# 03_ZYNQ_Power.net
KiCad netlist of a schematic drawn in Altium Designer
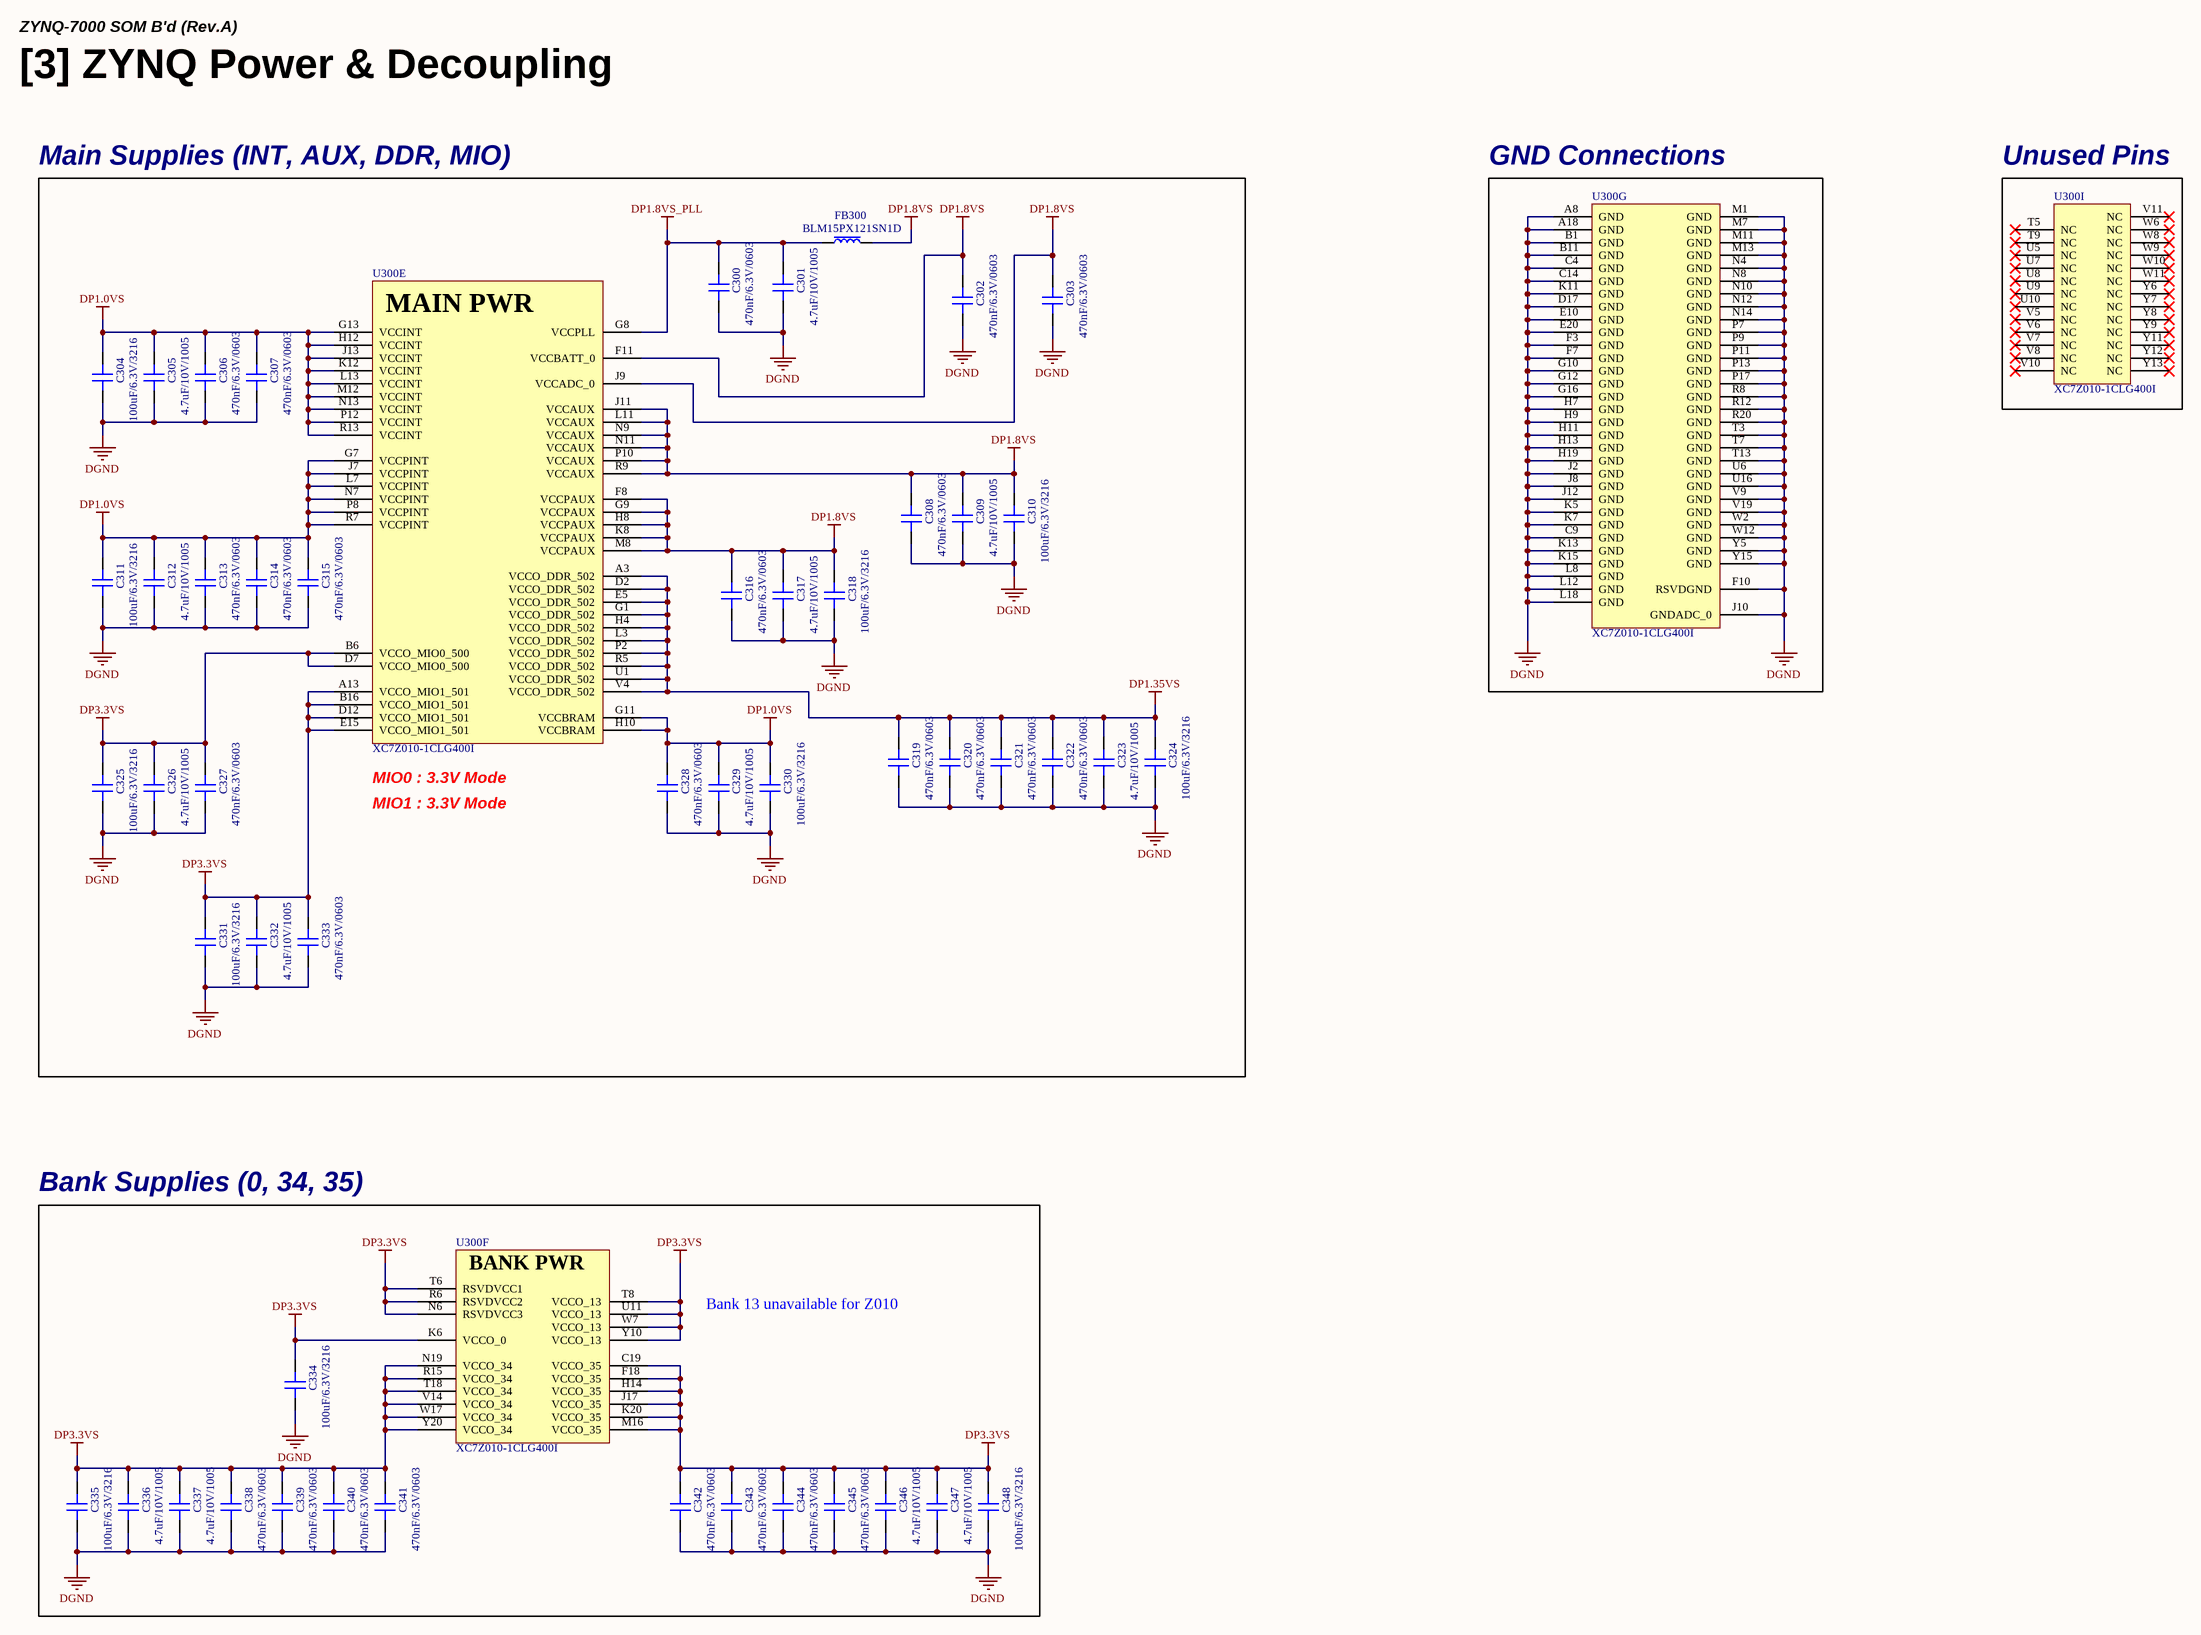
[diagram p0: 03_ZYNQ_Power.SchDoc]

(export (version "E")
  (design (tool "Eeschema 10.0.6"))
  (components
    (comp (ref "C300")
      (value "470nF/6.3V/0603")
      (footprint "CAP 0603 (0201_INCH)")
      (description "6.3V 470nF X5R ±10% 0201  Multilayer Ceramic Capacitors MLCC - SMD/SMT ROHS")
      (fields (field (name "LCSC PART #") "C85926"))
      (libsource (lib "Arkx") (part "CAP_470nF/6.3V/0603"))
    )
    (comp (ref "C301")
      (value "4.7uF/10V/1005")
      (footprint "CAP 1005 (0402_INCH)")
      (description "10V 4.7uF X5R ±20% 0402  Multilayer Ceramic Capacitors MLCC - SMD/SMT ROHS")
      (fields (field (name "LCSC PART #") "C23733"))
      (libsource (lib "Arkx") (part "CAP_4.7uF/10V/1005"))
    )
    (comp (ref "C302")
      (value "470nF/6.3V/0603")
      (footprint "CAP 0603 (0201_INCH)")
      (description "6.3V 470nF X5R ±10% 0201  Multilayer Ceramic Capacitors MLCC - SMD/SMT ROHS")
      (fields (field (name "LCSC PART #") "C85926"))
      (libsource (lib "Arkx") (part "CAP_470nF/6.3V/0603"))
    )
    (comp (ref "C303")
      (value "470nF/6.3V/0603")
      (footprint "CAP 0603 (0201_INCH)")
      (description "6.3V 470nF X5R ±10% 0201  Multilayer Ceramic Capacitors MLCC - SMD/SMT ROHS")
      (fields (field (name "LCSC PART #") "C85926"))
      (libsource (lib "Arkx") (part "CAP_470nF/6.3V/0603"))
    )
    (comp (ref "C304")
      (value "100uF/6.3V/3216")
      (footprint "CAP 3216 (1206_INCH) - H1.8MM")
      (description "Ceramic CAP_100uF/6.3V/3216")
      (fields (field (name "LCSC PART #") "C15008"))
      (libsource (lib "Arkx") (part "CAP_100uF/6.3V/3216"))
    )
    (comp (ref "C305")
      (value "4.7uF/10V/1005")
      (footprint "CAP 1005 (0402_INCH)")
      (description "10V 4.7uF X5R ±20% 0402  Multilayer Ceramic Capacitors MLCC - SMD/SMT ROHS")
      (fields (field (name "LCSC PART #") "C23733"))
      (libsource (lib "Arkx") (part "CAP_4.7uF/10V/1005"))
    )
    (comp (ref "C306")
      (value "470nF/6.3V/0603")
      (footprint "CAP 0603 (0201_INCH)")
      (description "6.3V 470nF X5R ±10% 0201  Multilayer Ceramic Capacitors MLCC - SMD/SMT ROHS")
      (fields (field (name "LCSC PART #") "C85926"))
      (libsource (lib "Arkx") (part "CAP_470nF/6.3V/0603"))
    )
    (comp (ref "C307")
      (value "470nF/6.3V/0603")
      (footprint "CAP 0603 (0201_INCH)")
      (description "6.3V 470nF X5R ±10% 0201  Multilayer Ceramic Capacitors MLCC - SMD/SMT ROHS")
      (fields (field (name "LCSC PART #") "C85926"))
      (libsource (lib "Arkx") (part "CAP_470nF/6.3V/0603"))
    )
    (comp (ref "C308")
      (value "470nF/6.3V/0603")
      (footprint "CAP 0603 (0201_INCH)")
      (description "6.3V 470nF X5R ±10% 0201  Multilayer Ceramic Capacitors MLCC - SMD/SMT ROHS")
      (fields (field (name "LCSC PART #") "C85926"))
      (libsource (lib "Arkx") (part "CAP_470nF/6.3V/0603"))
    )
    (comp (ref "C309")
      (value "4.7uF/10V/1005")
      (footprint "CAP 1005 (0402_INCH)")
      (description "10V 4.7uF X5R ±20% 0402  Multilayer Ceramic Capacitors MLCC - SMD/SMT ROHS")
      (fields (field (name "LCSC PART #") "C23733"))
      (libsource (lib "Arkx") (part "CAP_4.7uF/10V/1005"))
    )
    (comp (ref "C310")
      (value "100uF/6.3V/3216")
      (footprint "CAP 3216 (1206_INCH) - H1.8MM")
      (description "Ceramic CAP_100uF/6.3V/3216")
      (fields (field (name "LCSC PART #") "C15008"))
      (libsource (lib "Arkx") (part "CAP_100uF/6.3V/3216"))
    )
    (comp (ref "C311")
      (value "100uF/6.3V/3216")
      (footprint "CAP 3216 (1206_INCH) - H1.8MM")
      (description "Ceramic CAP_100uF/6.3V/3216")
      (fields (field (name "LCSC PART #") "C15008"))
      (libsource (lib "Arkx") (part "CAP_100uF/6.3V/3216"))
    )
    (comp (ref "C312")
      (value "4.7uF/10V/1005")
      (footprint "CAP 1005 (0402_INCH)")
      (description "10V 4.7uF X5R ±20% 0402  Multilayer Ceramic Capacitors MLCC - SMD/SMT ROHS")
      (fields (field (name "LCSC PART #") "C23733"))
      (libsource (lib "Arkx") (part "CAP_4.7uF/10V/1005"))
    )
    (comp (ref "C313")
      (value "470nF/6.3V/0603")
      (footprint "CAP 0603 (0201_INCH)")
      (description "6.3V 470nF X5R ±10% 0201  Multilayer Ceramic Capacitors MLCC - SMD/SMT ROHS")
      (fields (field (name "LCSC PART #") "C85926"))
      (libsource (lib "Arkx") (part "CAP_470nF/6.3V/0603"))
    )
    (comp (ref "C314")
      (value "470nF/6.3V/0603")
      (footprint "CAP 0603 (0201_INCH)")
      (description "6.3V 470nF X5R ±10% 0201  Multilayer Ceramic Capacitors MLCC - SMD/SMT ROHS")
      (fields (field (name "LCSC PART #") "C85926"))
      (libsource (lib "Arkx") (part "CAP_470nF/6.3V/0603"))
    )
    (comp (ref "C315")
      (value "470nF/6.3V/0603")
      (footprint "CAP 0603 (0201_INCH)")
      (description "6.3V 470nF X5R ±10% 0201  Multilayer Ceramic Capacitors MLCC - SMD/SMT ROHS")
      (fields (field (name "LCSC PART #") "C85926"))
      (libsource (lib "Arkx") (part "CAP_470nF/6.3V/0603"))
    )
    (comp (ref "C316")
      (value "470nF/6.3V/0603")
      (footprint "CAP 0603 (0201_INCH)")
      (description "6.3V 470nF X5R ±10% 0201  Multilayer Ceramic Capacitors MLCC - SMD/SMT ROHS")
      (fields (field (name "LCSC PART #") "C85926"))
      (libsource (lib "Arkx") (part "CAP_470nF/6.3V/0603"))
    )
    (comp (ref "C317")
      (value "4.7uF/10V/1005")
      (footprint "CAP 1005 (0402_INCH)")
      (description "10V 4.7uF X5R ±20% 0402  Multilayer Ceramic Capacitors MLCC - SMD/SMT ROHS")
      (fields (field (name "LCSC PART #") "C23733"))
      (libsource (lib "Arkx") (part "CAP_4.7uF/10V/1005"))
    )
    (comp (ref "C318")
      (value "100uF/6.3V/3216")
      (footprint "CAP 3216 (1206_INCH) - H1.8MM")
      (description "Ceramic CAP_100uF/6.3V/3216")
      (fields (field (name "LCSC PART #") "C15008"))
      (libsource (lib "Arkx") (part "CAP_100uF/6.3V/3216"))
    )
    (comp (ref "C319")
      (value "470nF/6.3V/0603")
      (footprint "CAP 0603 (0201_INCH)")
      (description "6.3V 470nF X5R ±10% 0201  Multilayer Ceramic Capacitors MLCC - SMD/SMT ROHS")
      (fields (field (name "LCSC PART #") "C85926"))
      (libsource (lib "Arkx") (part "CAP_470nF/6.3V/0603"))
    )
    (comp (ref "C320")
      (value "470nF/6.3V/0603")
      (footprint "CAP 0603 (0201_INCH)")
      (description "6.3V 470nF X5R ±10% 0201  Multilayer Ceramic Capacitors MLCC - SMD/SMT ROHS")
      (fields (field (name "LCSC PART #") "C85926"))
      (libsource (lib "Arkx") (part "CAP_470nF/6.3V/0603"))
    )
    (comp (ref "C321")
      (value "470nF/6.3V/0603")
      (footprint "CAP 0603 (0201_INCH)")
      (description "6.3V 470nF X5R ±10% 0201  Multilayer Ceramic Capacitors MLCC - SMD/SMT ROHS")
      (fields (field (name "LCSC PART #") "C85926"))
      (libsource (lib "Arkx") (part "CAP_470nF/6.3V/0603"))
    )
    (comp (ref "C322")
      (value "470nF/6.3V/0603")
      (footprint "CAP 0603 (0201_INCH)")
      (description "6.3V 470nF X5R ±10% 0201  Multilayer Ceramic Capacitors MLCC - SMD/SMT ROHS")
      (fields (field (name "LCSC PART #") "C85926"))
      (libsource (lib "Arkx") (part "CAP_470nF/6.3V/0603"))
    )
    (comp (ref "C323")
      (value "4.7uF/10V/1005")
      (footprint "CAP 1005 (0402_INCH)")
      (description "10V 4.7uF X5R ±20% 0402  Multilayer Ceramic Capacitors MLCC - SMD/SMT ROHS")
      (fields (field (name "LCSC PART #") "C23733"))
      (libsource (lib "Arkx") (part "CAP_4.7uF/10V/1005"))
    )
    (comp (ref "C324")
      (value "100uF/6.3V/3216")
      (footprint "CAP 3216 (1206_INCH) - H1.8MM")
      (description "Ceramic CAP_100uF/6.3V/3216")
      (fields (field (name "LCSC PART #") "C15008"))
      (libsource (lib "Arkx") (part "CAP_100uF/6.3V/3216"))
    )
    (comp (ref "C325")
      (value "100uF/6.3V/3216")
      (footprint "CAP 3216 (1206_INCH) - H1.8MM")
      (description "Ceramic CAP_100uF/6.3V/3216")
      (fields (field (name "LCSC PART #") "C15008"))
      (libsource (lib "Arkx") (part "CAP_100uF/6.3V/3216"))
    )
    (comp (ref "C326")
      (value "4.7uF/10V/1005")
      (footprint "CAP 1005 (0402_INCH)")
      (description "10V 4.7uF X5R ±20% 0402  Multilayer Ceramic Capacitors MLCC - SMD/SMT ROHS")
      (fields (field (name "LCSC PART #") "C23733"))
      (libsource (lib "Arkx") (part "CAP_4.7uF/10V/1005"))
    )
    (comp (ref "C327")
      (value "470nF/6.3V/0603")
      (footprint "CAP 0603 (0201_INCH)")
      (description "6.3V 470nF X5R ±10% 0201  Multilayer Ceramic Capacitors MLCC - SMD/SMT ROHS")
      (fields (field (name "LCSC PART #") "C85926"))
      (libsource (lib "Arkx") (part "CAP_470nF/6.3V/0603"))
    )
    (comp (ref "C328")
      (value "470nF/6.3V/0603")
      (footprint "CAP 0603 (0201_INCH)")
      (description "6.3V 470nF X5R ±10% 0201  Multilayer Ceramic Capacitors MLCC - SMD/SMT ROHS")
      (fields (field (name "LCSC PART #") "C85926"))
      (libsource (lib "Arkx") (part "CAP_470nF/6.3V/0603"))
    )
    (comp (ref "C329")
      (value "4.7uF/10V/1005")
      (footprint "CAP 1005 (0402_INCH)")
      (description "10V 4.7uF X5R ±20% 0402  Multilayer Ceramic Capacitors MLCC - SMD/SMT ROHS")
      (fields (field (name "LCSC PART #") "C23733"))
      (libsource (lib "Arkx") (part "CAP_4.7uF/10V/1005"))
    )
    (comp (ref "C330")
      (value "100uF/6.3V/3216")
      (footprint "CAP 3216 (1206_INCH) - H1.8MM")
      (description "Ceramic CAP_100uF/6.3V/3216")
      (fields (field (name "LCSC PART #") "C15008"))
      (libsource (lib "Arkx") (part "CAP_100uF/6.3V/3216"))
    )
    (comp (ref "C331")
      (value "100uF/6.3V/3216")
      (footprint "CAP 3216 (1206_INCH) - H1.8MM")
      (description "Ceramic CAP_100uF/6.3V/3216")
      (fields (field (name "LCSC PART #") "C15008"))
      (libsource (lib "Arkx") (part "CAP_100uF/6.3V/3216"))
    )
    (comp (ref "C332")
      (value "4.7uF/10V/1005")
      (footprint "CAP 1005 (0402_INCH)")
      (description "10V 4.7uF X5R ±20% 0402  Multilayer Ceramic Capacitors MLCC - SMD/SMT ROHS")
      (fields (field (name "LCSC PART #") "C23733"))
      (libsource (lib "Arkx") (part "CAP_4.7uF/10V/1005"))
    )
    (comp (ref "C333")
      (value "470nF/6.3V/0603")
      (footprint "CAP 0603 (0201_INCH)")
      (description "6.3V 470nF X5R ±10% 0201  Multilayer Ceramic Capacitors MLCC - SMD/SMT ROHS")
      (fields (field (name "LCSC PART #") "C85926"))
      (libsource (lib "Arkx") (part "CAP_470nF/6.3V/0603"))
    )
    (comp (ref "C334")
      (value "100uF/6.3V/3216")
      (footprint "CAP 3216 (1206_INCH) - H1.8MM")
      (description "Ceramic CAP_100uF/6.3V/3216")
      (fields (field (name "LCSC PART #") "C15008"))
      (libsource (lib "Arkx") (part "CAP_100uF/6.3V/3216"))
    )
    (comp (ref "C335")
      (value "100uF/6.3V/3216")
      (footprint "CAP 3216 (1206_INCH) - H1.8MM")
      (description "Ceramic CAP_100uF/6.3V/3216")
      (fields (field (name "LCSC PART #") "C15008"))
      (libsource (lib "Arkx") (part "CAP_100uF/6.3V/3216"))
    )
    (comp (ref "C336")
      (value "4.7uF/10V/1005")
      (footprint "CAP 1005 (0402_INCH)")
      (description "10V 4.7uF X5R ±20% 0402  Multilayer Ceramic Capacitors MLCC - SMD/SMT ROHS")
      (fields (field (name "LCSC PART #") "C23733"))
      (libsource (lib "Arkx") (part "CAP_4.7uF/10V/1005"))
    )
    (comp (ref "C337")
      (value "4.7uF/10V/1005")
      (footprint "CAP 1005 (0402_INCH)")
      (description "10V 4.7uF X5R ±20% 0402  Multilayer Ceramic Capacitors MLCC - SMD/SMT ROHS")
      (fields (field (name "LCSC PART #") "C23733"))
      (libsource (lib "Arkx") (part "CAP_4.7uF/10V/1005"))
    )
    (comp (ref "C338")
      (value "470nF/6.3V/0603")
      (footprint "CAP 0603 (0201_INCH)")
      (description "6.3V 470nF X5R ±10% 0201  Multilayer Ceramic Capacitors MLCC - SMD/SMT ROHS")
      (fields (field (name "LCSC PART #") "C85926"))
      (libsource (lib "Arkx") (part "CAP_470nF/6.3V/0603"))
    )
    (comp (ref "C339")
      (value "470nF/6.3V/0603")
      (footprint "CAP 0603 (0201_INCH)")
      (description "6.3V 470nF X5R ±10% 0201  Multilayer Ceramic Capacitors MLCC - SMD/SMT ROHS")
      (fields (field (name "LCSC PART #") "C85926"))
      (libsource (lib "Arkx") (part "CAP_470nF/6.3V/0603"))
    )
    (comp (ref "C340")
      (value "470nF/6.3V/0603")
      (footprint "CAP 0603 (0201_INCH)")
      (description "6.3V 470nF X5R ±10% 0201  Multilayer Ceramic Capacitors MLCC - SMD/SMT ROHS")
      (fields (field (name "LCSC PART #") "C85926"))
      (libsource (lib "Arkx") (part "CAP_470nF/6.3V/0603"))
    )
    (comp (ref "C341")
      (value "470nF/6.3V/0603")
      (footprint "CAP 0603 (0201_INCH)")
      (description "6.3V 470nF X5R ±10% 0201  Multilayer Ceramic Capacitors MLCC - SMD/SMT ROHS")
      (fields (field (name "LCSC PART #") "C85926"))
      (libsource (lib "Arkx") (part "CAP_470nF/6.3V/0603"))
    )
    (comp (ref "C342")
      (value "470nF/6.3V/0603")
      (footprint "CAP 0603 (0201_INCH)")
      (description "6.3V 470nF X5R ±10% 0201  Multilayer Ceramic Capacitors MLCC - SMD/SMT ROHS")
      (fields (field (name "LCSC PART #") "C85926"))
      (libsource (lib "Arkx") (part "CAP_470nF/6.3V/0603"))
    )
    (comp (ref "C343")
      (value "470nF/6.3V/0603")
      (footprint "CAP 0603 (0201_INCH)")
      (description "6.3V 470nF X5R ±10% 0201  Multilayer Ceramic Capacitors MLCC - SMD/SMT ROHS")
      (fields (field (name "LCSC PART #") "C85926"))
      (libsource (lib "Arkx") (part "CAP_470nF/6.3V/0603"))
    )
    (comp (ref "C344")
      (value "470nF/6.3V/0603")
      (footprint "CAP 0603 (0201_INCH)")
      (description "6.3V 470nF X5R ±10% 0201  Multilayer Ceramic Capacitors MLCC - SMD/SMT ROHS")
      (fields (field (name "LCSC PART #") "C85926"))
      (libsource (lib "Arkx") (part "CAP_470nF/6.3V/0603"))
    )
    (comp (ref "C345")
      (value "470nF/6.3V/0603")
      (footprint "CAP 0603 (0201_INCH)")
      (description "6.3V 470nF X5R ±10% 0201  Multilayer Ceramic Capacitors MLCC - SMD/SMT ROHS")
      (fields (field (name "LCSC PART #") "C85926"))
      (libsource (lib "Arkx") (part "CAP_470nF/6.3V/0603"))
    )
    (comp (ref "C346")
      (value "4.7uF/10V/1005")
      (footprint "CAP 1005 (0402_INCH)")
      (description "10V 4.7uF X5R ±20% 0402  Multilayer Ceramic Capacitors MLCC - SMD/SMT ROHS")
      (fields (field (name "LCSC PART #") "C23733"))
      (libsource (lib "Arkx") (part "CAP_4.7uF/10V/1005"))
    )
    (comp (ref "C347")
      (value "4.7uF/10V/1005")
      (footprint "CAP 1005 (0402_INCH)")
      (description "10V 4.7uF X5R ±20% 0402  Multilayer Ceramic Capacitors MLCC - SMD/SMT ROHS")
      (fields (field (name "LCSC PART #") "C23733"))
      (libsource (lib "Arkx") (part "CAP_4.7uF/10V/1005"))
    )
    (comp (ref "C348")
      (value "100uF/6.3V/3216")
      (footprint "CAP 3216 (1206_INCH) - H1.8MM")
      (description "Ceramic CAP_100uF/6.3V/3216")
      (fields (field (name "LCSC PART #") "C15008"))
      (libsource (lib "Arkx") (part "CAP_100uF/6.3V/3216"))
    )
    (comp (ref "FB300")
      (value "BLM15PX121SN1D")
      (footprint "FB 1005 (0402_inch)")
      (description "55mΩ ±25% 120Ω@100MHz 0402  Ferrite Beads ROHS")
      (fields (field (name "LCSC PART #") "C88970"))
      (libsource (lib "Arkx") (part "FB_BLM15PX121SN1D"))
    )
    (comp (ref "U300")
      (value "XC7Z010-1CLG400I")
      (footprint "IC_SOC_XC7Z010-1CLG400I")
      (fields (field (name "LCSC PART #") "C2840994"))
      (libsource (lib "Arkx") (part "IC_SOC_XC7Z010-1CLG400I"))
    )
  )
  (nets
    (net (code "1") (name "DGND") (class "Default")
      (node (ref "C300") (pin "1") (pinfunction "1_1") (pintype "passive"))
      (node (ref "C301") (pin "1") (pinfunction "1_1") (pintype "passive"))
      (node (ref "C302") (pin "1") (pinfunction "1_1") (pintype "passive"))
      (node (ref "C303") (pin "1") (pinfunction "1_1") (pintype "passive"))
      (node (ref "C304") (pin "1") (pinfunction "1_1") (pintype "passive"))
      (node (ref "C305") (pin "1") (pinfunction "1_1") (pintype "passive"))
      (node (ref "C306") (pin "1") (pinfunction "1_1") (pintype "passive"))
      (node (ref "C307") (pin "1") (pinfunction "1_1") (pintype "passive"))
      (node (ref "C308") (pin "1") (pinfunction "1_1") (pintype "passive"))
      (node (ref "C309") (pin "1") (pinfunction "1_1") (pintype "passive"))
      (node (ref "C310") (pin "1") (pinfunction "1_1") (pintype "passive"))
      (node (ref "C311") (pin "1") (pinfunction "1_1") (pintype "passive"))
      (node (ref "C312") (pin "1") (pinfunction "1_1") (pintype "passive"))
      (node (ref "C313") (pin "1") (pinfunction "1_1") (pintype "passive"))
      (node (ref "C314") (pin "1") (pinfunction "1_1") (pintype "passive"))
      (node (ref "C315") (pin "1") (pinfunction "1_1") (pintype "passive"))
      (node (ref "C316") (pin "1") (pinfunction "1_1") (pintype "passive"))
      (node (ref "C317") (pin "1") (pinfunction "1_1") (pintype "passive"))
      (node (ref "C318") (pin "1") (pinfunction "1_1") (pintype "passive"))
      (node (ref "C319") (pin "1") (pinfunction "1_1") (pintype "passive"))
      (node (ref "C320") (pin "1") (pinfunction "1_1") (pintype "passive"))
      (node (ref "C321") (pin "1") (pinfunction "1_1") (pintype "passive"))
      (node (ref "C322") (pin "1") (pinfunction "1_1") (pintype "passive"))
      (node (ref "C323") (pin "1") (pinfunction "1_1") (pintype "passive"))
      (node (ref "C324") (pin "1") (pinfunction "1_1") (pintype "passive"))
      (node (ref "C325") (pin "1") (pinfunction "1_1") (pintype "passive"))
      (node (ref "C326") (pin "1") (pinfunction "1_1") (pintype "passive"))
      (node (ref "C327") (pin "1") (pinfunction "1_1") (pintype "passive"))
      (node (ref "C328") (pin "1") (pinfunction "1_1") (pintype "passive"))
      (node (ref "C329") (pin "1") (pinfunction "1_1") (pintype "passive"))
      (node (ref "C330") (pin "1") (pinfunction "1_1") (pintype "passive"))
      (node (ref "C331") (pin "1") (pinfunction "1_1") (pintype "passive"))
      (node (ref "C332") (pin "1") (pinfunction "1_1") (pintype "passive"))
      (node (ref "C333") (pin "1") (pinfunction "1_1") (pintype "passive"))
      (node (ref "C334") (pin "1") (pinfunction "1_1") (pintype "passive"))
      (node (ref "C335") (pin "1") (pinfunction "1_1") (pintype "passive"))
      (node (ref "C336") (pin "1") (pinfunction "1_1") (pintype "passive"))
      (node (ref "C337") (pin "1") (pinfunction "1_1") (pintype "passive"))
      (node (ref "C338") (pin "1") (pinfunction "1_1") (pintype "passive"))
      (node (ref "C339") (pin "1") (pinfunction "1_1") (pintype "passive"))
      (node (ref "C340") (pin "1") (pinfunction "1_1") (pintype "passive"))
      (node (ref "C341") (pin "1") (pinfunction "1_1") (pintype "passive"))
      (node (ref "C342") (pin "1") (pinfunction "1_1") (pintype "passive"))
      (node (ref "C343") (pin "1") (pinfunction "1_1") (pintype "passive"))
      (node (ref "C344") (pin "1") (pinfunction "1_1") (pintype "passive"))
      (node (ref "C345") (pin "1") (pinfunction "1_1") (pintype "passive"))
      (node (ref "C346") (pin "1") (pinfunction "1_1") (pintype "passive"))
      (node (ref "C347") (pin "1") (pinfunction "1_1") (pintype "passive"))
      (node (ref "C348") (pin "1") (pinfunction "1_1") (pintype "passive"))
      (node (ref "U300") (pin "A18") (pinfunction "GND_A18") (pintype "power_in"))
      (node (ref "U300") (pin "A8") (pinfunction "GND_A8") (pintype "power_in"))
      (node (ref "U300") (pin "B1") (pinfunction "GND_B1") (pintype "power_in"))
      (node (ref "U300") (pin "B11") (pinfunction "GND_B11") (pintype "power_in"))
      (node (ref "U300") (pin "C14") (pinfunction "GND_C14") (pintype "power_in"))
      (node (ref "U300") (pin "C4") (pinfunction "GND_C4") (pintype "power_in"))
      (node (ref "U300") (pin "C9") (pinfunction "GND_C9") (pintype "power_in"))
      (node (ref "U300") (pin "D17") (pinfunction "GND_D17") (pintype "power_in"))
      (node (ref "U300") (pin "E10") (pinfunction "GND_E10") (pintype "power_in"))
      (node (ref "U300") (pin "E20") (pinfunction "GND_E20") (pintype "power_in"))
      (node (ref "U300") (pin "F10") (pinfunction "RSVDGND_F10") (pintype "power_in"))
      (node (ref "U300") (pin "F3") (pinfunction "GND_F3") (pintype "power_in"))
      (node (ref "U300") (pin "F7") (pinfunction "GND_F7") (pintype "power_in"))
      (node (ref "U300") (pin "G10") (pinfunction "GND_G10") (pintype "power_in"))
      (node (ref "U300") (pin "G12") (pinfunction "GND_G12") (pintype "power_in"))
      (node (ref "U300") (pin "G16") (pinfunction "GND_G16") (pintype "power_in"))
      (node (ref "U300") (pin "H11") (pinfunction "GND_H11") (pintype "power_in"))
      (node (ref "U300") (pin "H13") (pinfunction "GND_H13") (pintype "power_in"))
      (node (ref "U300") (pin "H19") (pinfunction "GND_H19") (pintype "power_in"))
      (node (ref "U300") (pin "H7") (pinfunction "GND_H7") (pintype "power_in"))
      (node (ref "U300") (pin "H9") (pinfunction "GND_H9") (pintype "power_in"))
      (node (ref "U300") (pin "J10") (pinfunction "GNDADC_0_J10") (pintype "power_in"))
      (node (ref "U300") (pin "J12") (pinfunction "GND_J12") (pintype "power_in"))
      (node (ref "U300") (pin "J2") (pinfunction "GND_J2") (pintype "power_in"))
      (node (ref "U300") (pin "J8") (pinfunction "GND_J8") (pintype "power_in"))
      (node (ref "U300") (pin "K11") (pinfunction "GND_K11") (pintype "power_in"))
      (node (ref "U300") (pin "K13") (pinfunction "GND_K13") (pintype "power_in"))
      (node (ref "U300") (pin "K15") (pinfunction "GND_K15") (pintype "power_in"))
      (node (ref "U300") (pin "K5") (pinfunction "GND_K5") (pintype "power_in"))
      (node (ref "U300") (pin "K7") (pinfunction "GND_K7") (pintype "power_in"))
      (node (ref "U300") (pin "L12") (pinfunction "GND_L12") (pintype "power_in"))
      (node (ref "U300") (pin "L18") (pinfunction "GND_L18") (pintype "power_in"))
      (node (ref "U300") (pin "L8") (pinfunction "GND_L8") (pintype "power_in"))
      (node (ref "U300") (pin "M1") (pinfunction "GND_M1") (pintype "power_in"))
      (node (ref "U300") (pin "M11") (pinfunction "GND_M11") (pintype "power_in"))
      (node (ref "U300") (pin "M13") (pinfunction "GND_M13") (pintype "power_in"))
      (node (ref "U300") (pin "M7") (pinfunction "GND_M7") (pintype "power_in"))
      (node (ref "U300") (pin "N10") (pinfunction "GND_N10") (pintype "power_in"))
      (node (ref "U300") (pin "N12") (pinfunction "GND_N12") (pintype "power_in"))
      (node (ref "U300") (pin "N14") (pinfunction "GND_N14") (pintype "power_in"))
      (node (ref "U300") (pin "N4") (pinfunction "GND_N4") (pintype "power_in"))
      (node (ref "U300") (pin "N8") (pinfunction "GND_N8") (pintype "power_in"))
      (node (ref "U300") (pin "P11") (pinfunction "GND_P11") (pintype "power_in"))
      (node (ref "U300") (pin "P13") (pinfunction "GND_P13") (pintype "power_in"))
      (node (ref "U300") (pin "P17") (pinfunction "GND_P17") (pintype "power_in"))
      (node (ref "U300") (pin "P7") (pinfunction "GND_P7") (pintype "power_in"))
      (node (ref "U300") (pin "P9") (pinfunction "GND_P9") (pintype "power_in"))
      (node (ref "U300") (pin "R12") (pinfunction "GND_R12") (pintype "power_in"))
      (node (ref "U300") (pin "R20") (pinfunction "GND_R20") (pintype "power_in"))
      (node (ref "U300") (pin "R8") (pinfunction "GND_R8") (pintype "power_in"))
      (node (ref "U300") (pin "T13") (pinfunction "GND_T13") (pintype "power_in"))
      (node (ref "U300") (pin "T3") (pinfunction "GND_T3") (pintype "power_in"))
      (node (ref "U300") (pin "T7") (pinfunction "GND_T7") (pintype "power_in"))
      (node (ref "U300") (pin "U16") (pinfunction "GND_U16") (pintype "power_in"))
      (node (ref "U300") (pin "U6") (pinfunction "GND_U6") (pintype "power_in"))
      (node (ref "U300") (pin "V19") (pinfunction "GND_V19") (pintype "power_in"))
      (node (ref "U300") (pin "V9") (pinfunction "GND_V9") (pintype "power_in"))
      (node (ref "U300") (pin "W12") (pinfunction "GND_W12") (pintype "power_in"))
      (node (ref "U300") (pin "W2") (pinfunction "GND_W2") (pintype "power_in"))
      (node (ref "U300") (pin "Y15") (pinfunction "GND_Y15") (pintype "power_in"))
      (node (ref "U300") (pin "Y5") (pinfunction "GND_Y5") (pintype "power_in"))
    )
    (net (code "2") (name "DP1.0VS") (class "Default")
      (node (ref "C304") (pin "2") (pinfunction "2_2") (pintype "passive"))
      (node (ref "C305") (pin "2") (pinfunction "2_2") (pintype "passive"))
      (node (ref "C306") (pin "2") (pinfunction "2_2") (pintype "passive"))
      (node (ref "C307") (pin "2") (pinfunction "2_2") (pintype "passive"))
      (node (ref "C311") (pin "2") (pinfunction "2_2") (pintype "passive"))
      (node (ref "C312") (pin "2") (pinfunction "2_2") (pintype "passive"))
      (node (ref "C313") (pin "2") (pinfunction "2_2") (pintype "passive"))
      (node (ref "C314") (pin "2") (pinfunction "2_2") (pintype "passive"))
      (node (ref "C315") (pin "2") (pinfunction "2_2") (pintype "passive"))
      (node (ref "C328") (pin "2") (pinfunction "2_2") (pintype "passive"))
      (node (ref "C329") (pin "2") (pinfunction "2_2") (pintype "passive"))
      (node (ref "C330") (pin "2") (pinfunction "2_2") (pintype "passive"))
      (node (ref "U300") (pin "G11") (pinfunction "VCCBRAM_G11") (pintype "power_in"))
      (node (ref "U300") (pin "G13") (pinfunction "VCCINT_G13") (pintype "power_in"))
      (node (ref "U300") (pin "G7") (pinfunction "VCCPINT_G7") (pintype "power_in"))
      (node (ref "U300") (pin "H10") (pinfunction "VCCBRAM_H10") (pintype "power_in"))
      (node (ref "U300") (pin "H12") (pinfunction "VCCINT_H12") (pintype "power_in"))
      (node (ref "U300") (pin "J13") (pinfunction "VCCINT_J13") (pintype "power_in"))
      (node (ref "U300") (pin "J7") (pinfunction "VCCPINT_J7") (pintype "power_in"))
      (node (ref "U300") (pin "K12") (pinfunction "VCCINT_K12") (pintype "power_in"))
      (node (ref "U300") (pin "L13") (pinfunction "VCCINT_L13") (pintype "power_in"))
      (node (ref "U300") (pin "L7") (pinfunction "VCCPINT_L7") (pintype "power_in"))
      (node (ref "U300") (pin "M12") (pinfunction "VCCINT_M12") (pintype "power_in"))
      (node (ref "U300") (pin "N13") (pinfunction "VCCINT_N13") (pintype "power_in"))
      (node (ref "U300") (pin "N7") (pinfunction "VCCPINT_N7") (pintype "power_in"))
      (node (ref "U300") (pin "P12") (pinfunction "VCCINT_P12") (pintype "power_in"))
      (node (ref "U300") (pin "P8") (pinfunction "VCCPINT_P8") (pintype "power_in"))
      (node (ref "U300") (pin "R13") (pinfunction "VCCINT_R13") (pintype "power_in"))
      (node (ref "U300") (pin "R7") (pinfunction "VCCPINT_R7") (pintype "power_in"))
    )
    (net (code "3") (name "DP1.8VS") (class "Default")
      (node (ref "C302") (pin "2") (pinfunction "2_2") (pintype "passive"))
      (node (ref "C303") (pin "2") (pinfunction "2_2") (pintype "passive"))
      (node (ref "C308") (pin "2") (pinfunction "2_2") (pintype "passive"))
      (node (ref "C309") (pin "2") (pinfunction "2_2") (pintype "passive"))
      (node (ref "C310") (pin "2") (pinfunction "2_2") (pintype "passive"))
      (node (ref "C316") (pin "2") (pinfunction "2_2") (pintype "passive"))
      (node (ref "C317") (pin "2") (pinfunction "2_2") (pintype "passive"))
      (node (ref "C318") (pin "2") (pinfunction "2_2") (pintype "passive"))
      (node (ref "FB300") (pin "2") (pinfunction "2_2") (pintype "passive"))
      (node (ref "U300") (pin "F11") (pinfunction "VCCBATT_0_F11") (pintype "power_in"))
      (node (ref "U300") (pin "F8") (pinfunction "VCCPAUX_F8") (pintype "power_in"))
      (node (ref "U300") (pin "G9") (pinfunction "VCCPAUX_G9") (pintype "power_in"))
      (node (ref "U300") (pin "H8") (pinfunction "VCCPAUX_H8") (pintype "power_in"))
      (node (ref "U300") (pin "J11") (pinfunction "VCCAUX_J11") (pintype "power_in"))
      (node (ref "U300") (pin "J9") (pinfunction "VCCADC_0_J9") (pintype "power_in"))
      (node (ref "U300") (pin "K8") (pinfunction "VCCPAUX_K8") (pintype "power_in"))
      (node (ref "U300") (pin "L11") (pinfunction "VCCAUX_L11") (pintype "power_in"))
      (node (ref "U300") (pin "M8") (pinfunction "VCCPAUX_M8") (pintype "power_in"))
      (node (ref "U300") (pin "N11") (pinfunction "VCCAUX_N11") (pintype "power_in"))
      (node (ref "U300") (pin "N9") (pinfunction "VCCAUX_N9") (pintype "power_in"))
      (node (ref "U300") (pin "P10") (pinfunction "VCCAUX_P10") (pintype "power_in"))
      (node (ref "U300") (pin "R9") (pinfunction "VCCAUX_R9") (pintype "power_in"))
    )
    (net (code "4") (name "DP1.8VS_PLL") (class "Default")
      (node (ref "C300") (pin "2") (pinfunction "2_2") (pintype "passive"))
      (node (ref "C301") (pin "2") (pinfunction "2_2") (pintype "passive"))
      (node (ref "FB300") (pin "1") (pinfunction "1_1") (pintype "passive"))
      (node (ref "U300") (pin "G8") (pinfunction "VCCPLL_G8") (pintype "power_in"))
    )
    (net (code "5") (name "DP1.35VS") (class "Default")
      (node (ref "C319") (pin "2") (pinfunction "2_2") (pintype "passive"))
      (node (ref "C320") (pin "2") (pinfunction "2_2") (pintype "passive"))
      (node (ref "C321") (pin "2") (pinfunction "2_2") (pintype "passive"))
      (node (ref "C322") (pin "2") (pinfunction "2_2") (pintype "passive"))
      (node (ref "C323") (pin "2") (pinfunction "2_2") (pintype "passive"))
      (node (ref "C324") (pin "2") (pinfunction "2_2") (pintype "passive"))
      (node (ref "U300") (pin "A3") (pinfunction "VCCO_DDR_502_A3") (pintype "power_in"))
      (node (ref "U300") (pin "D2") (pinfunction "VCCO_DDR_502_D2") (pintype "power_in"))
      (node (ref "U300") (pin "E5") (pinfunction "VCCO_DDR_502_E5") (pintype "power_in"))
      (node (ref "U300") (pin "G1") (pinfunction "VCCO_DDR_502_G1") (pintype "power_in"))
      (node (ref "U300") (pin "H4") (pinfunction "VCCO_DDR_502_H4") (pintype "power_in"))
      (node (ref "U300") (pin "L3") (pinfunction "VCCO_DDR_502_L3") (pintype "power_in"))
      (node (ref "U300") (pin "P2") (pinfunction "VCCO_DDR_502_P2") (pintype "power_in"))
      (node (ref "U300") (pin "R5") (pinfunction "VCCO_DDR_502_R5") (pintype "power_in"))
      (node (ref "U300") (pin "U1") (pinfunction "VCCO_DDR_502_U1") (pintype "power_in"))
      (node (ref "U300") (pin "V4") (pinfunction "VCCO_DDR_502_V4") (pintype "power_in"))
    )
    (net (code "6") (name "DP3.3VS") (class "Default")
      (node (ref "C325") (pin "2") (pinfunction "2_2") (pintype "passive"))
      (node (ref "C326") (pin "2") (pinfunction "2_2") (pintype "passive"))
      (node (ref "C327") (pin "2") (pinfunction "2_2") (pintype "passive"))
      (node (ref "C331") (pin "2") (pinfunction "2_2") (pintype "passive"))
      (node (ref "C332") (pin "2") (pinfunction "2_2") (pintype "passive"))
      (node (ref "C333") (pin "2") (pinfunction "2_2") (pintype "passive"))
      (node (ref "C334") (pin "2") (pinfunction "2_2") (pintype "passive"))
      (node (ref "C335") (pin "2") (pinfunction "2_2") (pintype "passive"))
      (node (ref "C336") (pin "2") (pinfunction "2_2") (pintype "passive"))
      (node (ref "C337") (pin "2") (pinfunction "2_2") (pintype "passive"))
      (node (ref "C338") (pin "2") (pinfunction "2_2") (pintype "passive"))
      (node (ref "C339") (pin "2") (pinfunction "2_2") (pintype "passive"))
      (node (ref "C340") (pin "2") (pinfunction "2_2") (pintype "passive"))
      (node (ref "C341") (pin "2") (pinfunction "2_2") (pintype "passive"))
      (node (ref "C342") (pin "2") (pinfunction "2_2") (pintype "passive"))
      (node (ref "C343") (pin "2") (pinfunction "2_2") (pintype "passive"))
      (node (ref "C344") (pin "2") (pinfunction "2_2") (pintype "passive"))
      (node (ref "C345") (pin "2") (pinfunction "2_2") (pintype "passive"))
      (node (ref "C346") (pin "2") (pinfunction "2_2") (pintype "passive"))
      (node (ref "C347") (pin "2") (pinfunction "2_2") (pintype "passive"))
      (node (ref "C348") (pin "2") (pinfunction "2_2") (pintype "passive"))
      (node (ref "U300") (pin "A13") (pinfunction "VCCO_MIO1_501_A13") (pintype "power_in"))
      (node (ref "U300") (pin "B16") (pinfunction "VCCO_MIO1_501_B16") (pintype "power_in"))
      (node (ref "U300") (pin "B6") (pinfunction "VCCO_MIO0_500_B6") (pintype "power_in"))
      (node (ref "U300") (pin "C19") (pinfunction "VCCO_35_C19") (pintype "power_in"))
      (node (ref "U300") (pin "D12") (pinfunction "VCCO_MIO1_501_D12") (pintype "power_in"))
      (node (ref "U300") (pin "D7") (pinfunction "VCCO_MIO0_500_D7") (pintype "power_in"))
      (node (ref "U300") (pin "E15") (pinfunction "VCCO_MIO1_501_E15") (pintype "power_in"))
      (node (ref "U300") (pin "F18") (pinfunction "VCCO_35_F18") (pintype "power_in"))
      (node (ref "U300") (pin "H14") (pinfunction "VCCO_35_H14") (pintype "power_in"))
      (node (ref "U300") (pin "J17") (pinfunction "VCCO_35_J17") (pintype "power_in"))
      (node (ref "U300") (pin "K20") (pinfunction "VCCO_35_K20") (pintype "power_in"))
      (node (ref "U300") (pin "K6") (pinfunction "VCCO_0_K6") (pintype "power_in"))
      (node (ref "U300") (pin "M16") (pinfunction "VCCO_35_M16") (pintype "power_in"))
      (node (ref "U300") (pin "N19") (pinfunction "VCCO_34_N19") (pintype "power_in"))
      (node (ref "U300") (pin "N6") (pinfunction "RSVDVCC3_N6") (pintype "power_in"))
      (node (ref "U300") (pin "R15") (pinfunction "VCCO_34_R15") (pintype "power_in"))
      (node (ref "U300") (pin "R6") (pinfunction "RSVDVCC2_R6") (pintype "power_in"))
      (node (ref "U300") (pin "T18") (pinfunction "VCCO_34_T18") (pintype "power_in"))
      (node (ref "U300") (pin "T6") (pinfunction "RSVDVCC1_T6") (pintype "power_in"))
      (node (ref "U300") (pin "T8") (pinfunction "VCCO_13_T8") (pintype "power_in"))
      (node (ref "U300") (pin "U11") (pinfunction "VCCO_13_U11") (pintype "power_in"))
      (node (ref "U300") (pin "V14") (pinfunction "VCCO_34_V14") (pintype "power_in"))
      (node (ref "U300") (pin "W17") (pinfunction "VCCO_34_W17") (pintype "power_in"))
      (node (ref "U300") (pin "W7") (pinfunction "VCCO_13_W7") (pintype "power_in"))
      (node (ref "U300") (pin "Y10") (pinfunction "VCCO_13_Y10") (pintype "power_in"))
      (node (ref "U300") (pin "Y20") (pinfunction "VCCO_34_Y20") (pintype "power_in"))
    )
    (net (code "7") (name "unconnected-(U300I-NC-PadT5)") (class "Default")
      (node (ref "U300") (pin "T5") (pinfunction "NC_T5") (pintype "tri_state+no_connect"))
    )
    (net (code "8") (name "unconnected-(U300I-NC-PadT9)") (class "Default")
      (node (ref "U300") (pin "T9") (pinfunction "NC_T9") (pintype "tri_state+no_connect"))
    )
    (net (code "9") (name "unconnected-(U300I-NC-PadU5)") (class "Default")
      (node (ref "U300") (pin "U5") (pinfunction "NC_U5") (pintype "tri_state+no_connect"))
    )
    (net (code "10") (name "unconnected-(U300I-NC-PadU7)") (class "Default")
      (node (ref "U300") (pin "U7") (pinfunction "NC_U7") (pintype "tri_state+no_connect"))
    )
    (net (code "11") (name "unconnected-(U300I-NC-PadU8)") (class "Default")
      (node (ref "U300") (pin "U8") (pinfunction "NC_U8") (pintype "tri_state+no_connect"))
    )
    (net (code "12") (name "unconnected-(U300I-NC-PadU9)") (class "Default")
      (node (ref "U300") (pin "U9") (pinfunction "NC_U9") (pintype "tri_state+no_connect"))
    )
    (net (code "13") (name "unconnected-(U300I-NC-PadU10)") (class "Default")
      (node (ref "U300") (pin "U10") (pinfunction "NC_U10") (pintype "tri_state+no_connect"))
    )
    (net (code "14") (name "unconnected-(U300I-NC-PadV5)") (class "Default")
      (node (ref "U300") (pin "V5") (pinfunction "NC_V5") (pintype "tri_state+no_connect"))
    )
    (net (code "15") (name "unconnected-(U300I-NC-PadV6)") (class "Default")
      (node (ref "U300") (pin "V6") (pinfunction "NC_V6") (pintype "tri_state+no_connect"))
    )
    (net (code "16") (name "unconnected-(U300I-NC-PadV7)") (class "Default")
      (node (ref "U300") (pin "V7") (pinfunction "NC_V7") (pintype "tri_state+no_connect"))
    )
    (net (code "17") (name "unconnected-(U300I-NC-PadV8)") (class "Default")
      (node (ref "U300") (pin "V8") (pinfunction "NC_V8") (pintype "tri_state+no_connect"))
    )
    (net (code "18") (name "unconnected-(U300I-NC-PadV10)") (class "Default")
      (node (ref "U300") (pin "V10") (pinfunction "NC_V10") (pintype "tri_state+no_connect"))
    )
    (net (code "19") (name "unconnected-(U300I-NC-PadV11)") (class "Default")
      (node (ref "U300") (pin "V11") (pinfunction "NC_V11") (pintype "tri_state+no_connect"))
    )
    (net (code "20") (name "unconnected-(U300I-NC-PadW6)") (class "Default")
      (node (ref "U300") (pin "W6") (pinfunction "NC_W6") (pintype "tri_state+no_connect"))
    )
    (net (code "21") (name "unconnected-(U300I-NC-PadW8)") (class "Default")
      (node (ref "U300") (pin "W8") (pinfunction "NC_W8") (pintype "tri_state+no_connect"))
    )
    (net (code "22") (name "unconnected-(U300I-NC-PadW9)") (class "Default")
      (node (ref "U300") (pin "W9") (pinfunction "NC_W9") (pintype "tri_state+no_connect"))
    )
    (net (code "23") (name "unconnected-(U300I-NC-PadW10)") (class "Default")
      (node (ref "U300") (pin "W10") (pinfunction "NC_W10") (pintype "tri_state+no_connect"))
    )
    (net (code "24") (name "unconnected-(U300I-NC-PadW11)") (class "Default")
      (node (ref "U300") (pin "W11") (pinfunction "NC_W11") (pintype "tri_state+no_connect"))
    )
    (net (code "25") (name "unconnected-(U300I-NC-PadY6)") (class "Default")
      (node (ref "U300") (pin "Y6") (pinfunction "NC_Y6") (pintype "tri_state+no_connect"))
    )
    (net (code "26") (name "unconnected-(U300I-NC-PadY7)") (class "Default")
      (node (ref "U300") (pin "Y7") (pinfunction "NC_Y7") (pintype "tri_state+no_connect"))
    )
    (net (code "27") (name "unconnected-(U300I-NC-PadY8)") (class "Default")
      (node (ref "U300") (pin "Y8") (pinfunction "NC_Y8") (pintype "tri_state+no_connect"))
    )
    (net (code "28") (name "unconnected-(U300I-NC-PadY9)") (class "Default")
      (node (ref "U300") (pin "Y9") (pinfunction "NC_Y9") (pintype "tri_state+no_connect"))
    )
    (net (code "29") (name "unconnected-(U300I-NC-PadY11)") (class "Default")
      (node (ref "U300") (pin "Y11") (pinfunction "NC_Y11") (pintype "tri_state+no_connect"))
    )
    (net (code "30") (name "unconnected-(U300I-NC-PadY12)") (class "Default")
      (node (ref "U300") (pin "Y12") (pinfunction "NC_Y12") (pintype "tri_state+no_connect"))
    )
    (net (code "31") (name "unconnected-(U300I-NC-PadY13)") (class "Default")
      (node (ref "U300") (pin "Y13") (pinfunction "NC_Y13") (pintype "tri_state+no_connect"))
    )
  )
)
